# tof.net
KiCad netlist of a schematic drawn in EAGLE
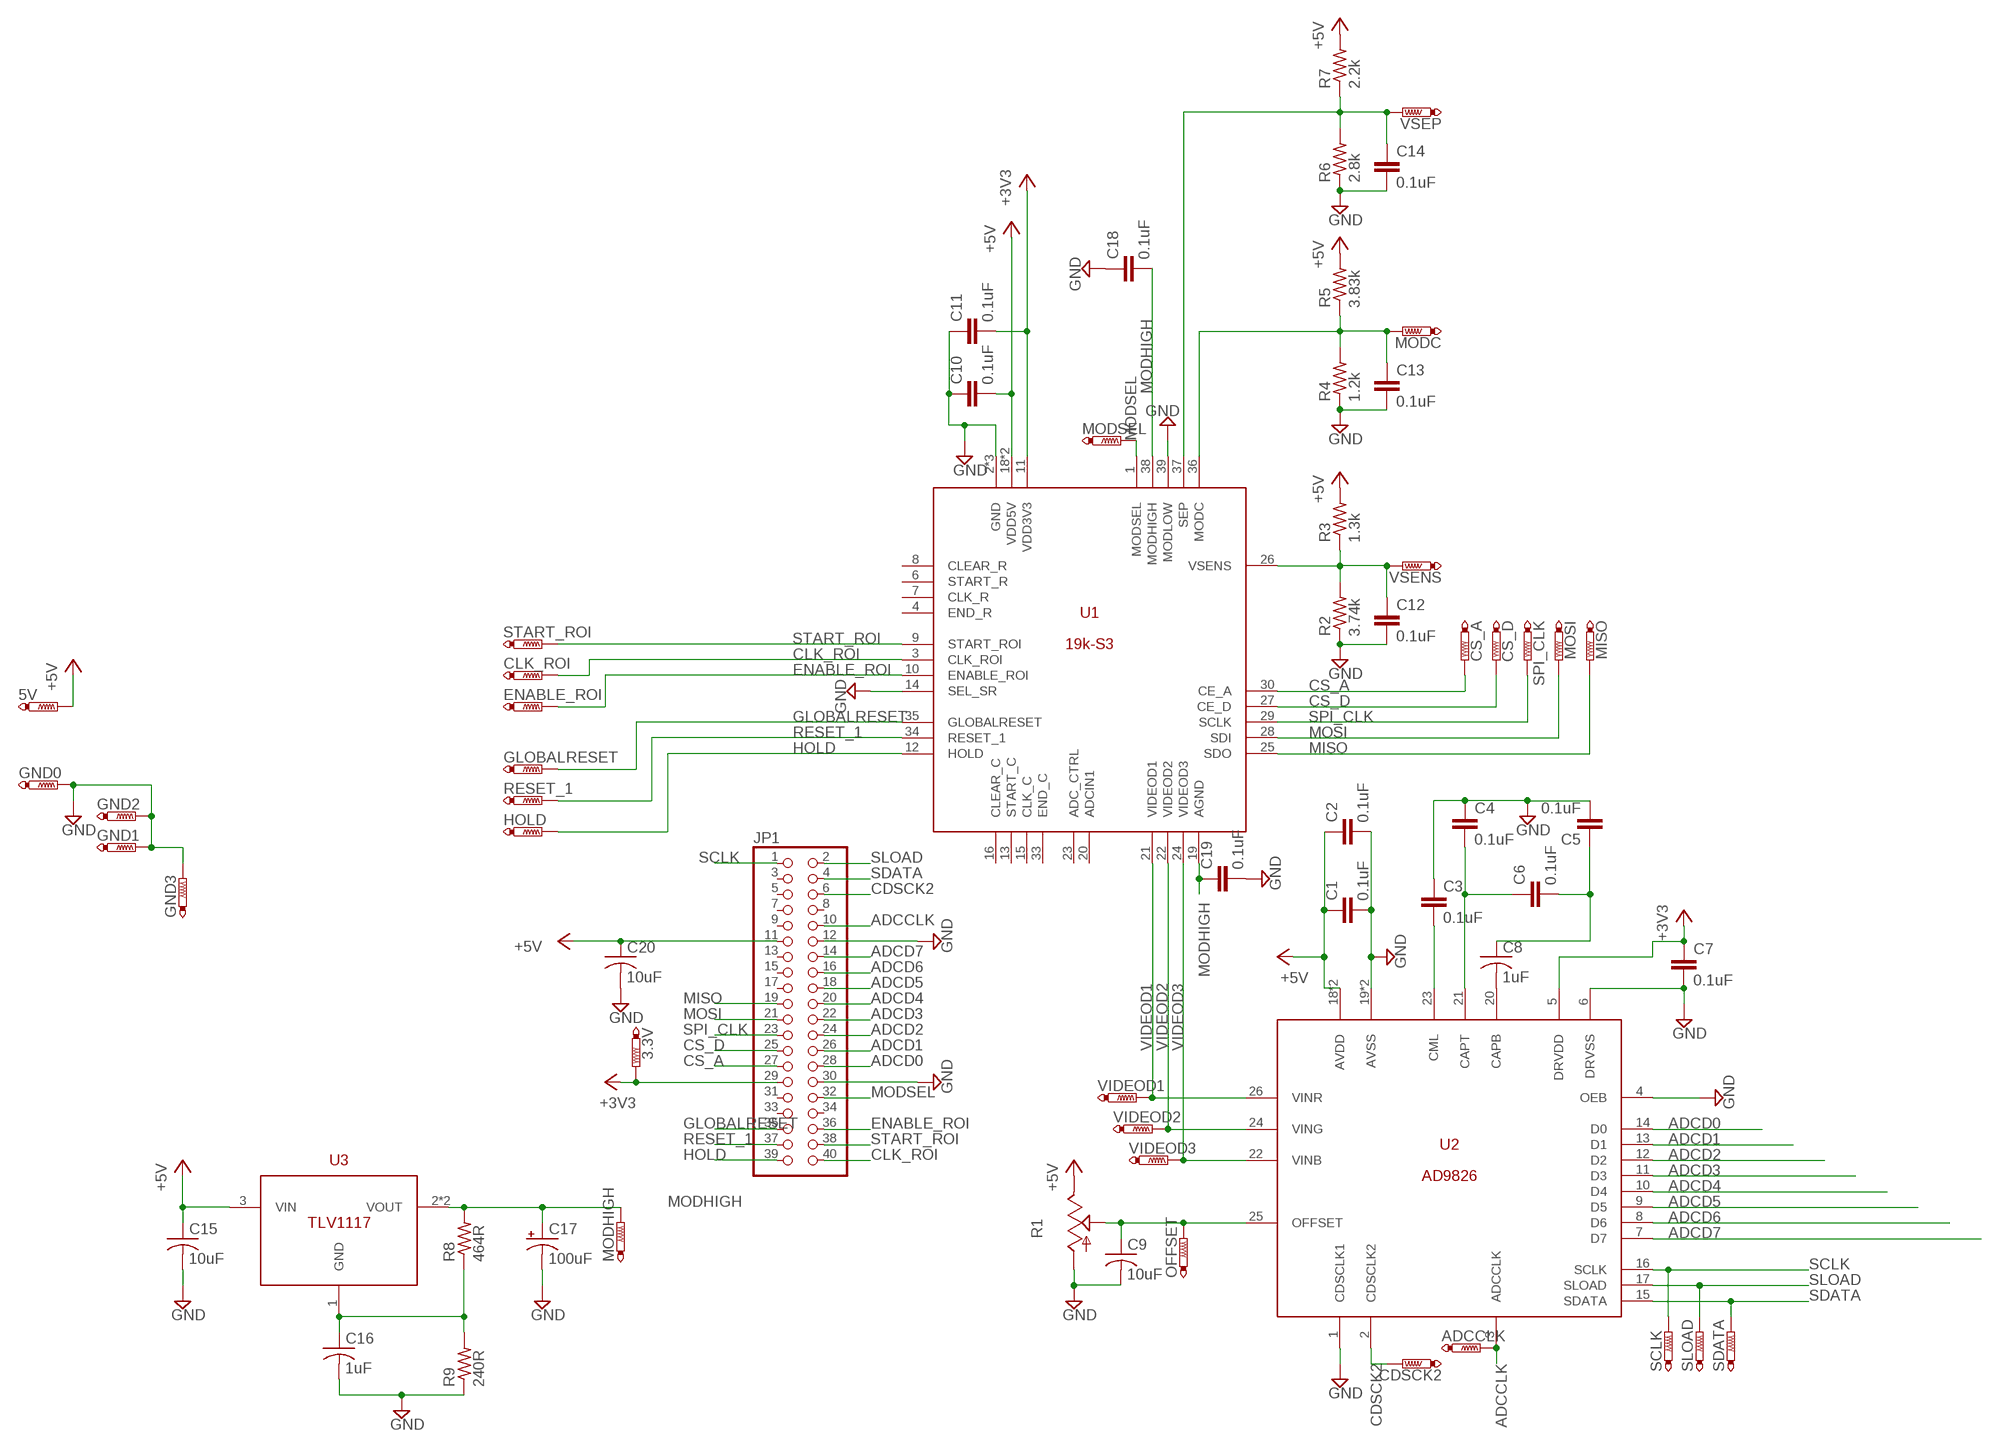
[diagram p0: schematic, sheet 1]

(export (version "E")
  (design (tool "Eeschema 10.0.6"))
  (components
    (comp (ref "3.3V")
      (value "PTR1PAD1-13")
      (footprint "eagle-import:P1-13")
      (libsource (lib "eagle-import") (part "PTR1PAD1-13"))
    )
    (comp (ref "5V")
      (value "PTR1PAD1-13")
      (footprint "eagle-import:P1-13")
      (libsource (lib "eagle-import") (part "PTR1PAD1-13"))
    )
    (comp (ref "ADCCLK")
      (value "PTR1PAD1-13")
      (footprint "eagle-import:P1-13")
      (libsource (lib "eagle-import") (part "PTR1PAD1-13"))
    )
    (comp (ref "C1")
      (value "0.1uF")
      (footprint "eagle-import:C0805")
      (libsource (lib "eagle-import") (part "C-EUC0805"))
    )
    (comp (ref "C2")
      (value "0.1uF")
      (footprint "eagle-import:C0805")
      (libsource (lib "eagle-import") (part "C-EUC0805"))
    )
    (comp (ref "C3")
      (value "0.1uF")
      (footprint "eagle-import:C0805")
      (libsource (lib "eagle-import") (part "C-EUC0805"))
    )
    (comp (ref "C4")
      (value "0.1uF")
      (footprint "eagle-import:C0805")
      (libsource (lib "eagle-import") (part "C-EUC0805"))
    )
    (comp (ref "C5")
      (value "0.1uF")
      (footprint "eagle-import:C0805")
      (libsource (lib "eagle-import") (part "C-EUC0805"))
    )
    (comp (ref "C6")
      (value "0.1uF")
      (footprint "eagle-import:C0805")
      (libsource (lib "eagle-import") (part "C-EUC0805"))
    )
    (comp (ref "C7")
      (value "0.1uF")
      (footprint "eagle-import:C0805")
      (libsource (lib "eagle-import") (part "C-EUC0805"))
    )
    (comp (ref "C8")
      (value "1uF")
      (footprint "eagle-import:C0805")
      (libsource (lib "eagle-import") (part "C-USC0805"))
    )
    (comp (ref "C9")
      (value "10uF")
      (footprint "eagle-import:C0805")
      (libsource (lib "eagle-import") (part "C-USC0805"))
    )
    (comp (ref "C10")
      (value "0.1uF")
      (footprint "eagle-import:C0805")
      (libsource (lib "eagle-import") (part "C-EUC0805"))
    )
    (comp (ref "C11")
      (value "0.1uF")
      (footprint "eagle-import:C0805")
      (libsource (lib "eagle-import") (part "C-EUC0805"))
    )
    (comp (ref "C12")
      (value "0.1uF")
      (footprint "eagle-import:C0805")
      (libsource (lib "eagle-import") (part "C-EUC0805"))
    )
    (comp (ref "C13")
      (value "0.1uF")
      (footprint "eagle-import:C0805")
      (libsource (lib "eagle-import") (part "C-EUC0805"))
    )
    (comp (ref "C14")
      (value "0.1uF")
      (footprint "eagle-import:C0805")
      (libsource (lib "eagle-import") (part "C-EUC0805"))
    )
    (comp (ref "C15")
      (value "10uF")
      (footprint "eagle-import:C0805")
      (libsource (lib "eagle-import") (part "C-USC0805"))
    )
    (comp (ref "C16")
      (value "1uF")
      (footprint "eagle-import:C0805")
      (libsource (lib "eagle-import") (part "C-USC0805"))
    )
    (comp (ref "C17")
      (value "100uF")
      (footprint "eagle-import:PANASONIC_F")
      (libsource (lib "eagle-import") (part "CPOL-USF"))
    )
    (comp (ref "C18")
      (value "0.1uF")
      (footprint "eagle-import:C0805")
      (libsource (lib "eagle-import") (part "C-EUC0805"))
    )
    (comp (ref "C19")
      (value "0.1uF")
      (footprint "eagle-import:C0805")
      (libsource (lib "eagle-import") (part "C-EUC0805"))
    )
    (comp (ref "C20")
      (value "10uF")
      (footprint "eagle-import:C0805")
      (libsource (lib "eagle-import") (part "C-USC0805"))
    )
    (comp (ref "CDSCK2")
      (value "PTR1PAD1-13")
      (footprint "eagle-import:P1-13")
      (libsource (lib "eagle-import") (part "PTR1PAD1-13"))
    )
    (comp (ref "CLK_ROI")
      (value "PTR1PAD1-13")
      (footprint "eagle-import:P1-13")
      (libsource (lib "eagle-import") (part "PTR1PAD1-13"))
    )
    (comp (ref "CS_A")
      (value "PTR1PAD1-13")
      (footprint "eagle-import:P1-13")
      (libsource (lib "eagle-import") (part "PTR1PAD1-13"))
    )
    (comp (ref "CS_D")
      (value "PTR1PAD1-13")
      (footprint "eagle-import:P1-13")
      (libsource (lib "eagle-import") (part "PTR1PAD1-13"))
    )
    (comp (ref "ENABLE_ROI")
      (value "PTR1PAD1-13")
      (footprint "eagle-import:P1-13")
      (libsource (lib "eagle-import") (part "PTR1PAD1-13"))
    )
    (comp (ref "GLOBALRESET")
      (value "PTR1PAD1-13")
      (footprint "eagle-import:P1-13")
      (libsource (lib "eagle-import") (part "PTR1PAD1-13"))
    )
    (comp (ref "GND0")
      (value "PTR1PAD1-13")
      (footprint "eagle-import:P1-13")
      (libsource (lib "eagle-import") (part "PTR1PAD1-13"))
    )
    (comp (ref "GND1")
      (value "PTR1PAD1-13")
      (footprint "eagle-import:P1-13")
      (libsource (lib "eagle-import") (part "PTR1PAD1-13"))
    )
    (comp (ref "GND2")
      (value "PTR1PAD1-13")
      (footprint "eagle-import:P1-13")
      (libsource (lib "eagle-import") (part "PTR1PAD1-13"))
    )
    (comp (ref "GND3")
      (value "PTR1PAD1-13")
      (footprint "eagle-import:P1-13")
      (libsource (lib "eagle-import") (part "PTR1PAD1-13"))
    )
    (comp (ref "HOLD")
      (value "PTR1PAD1-13")
      (footprint "eagle-import:P1-13")
      (libsource (lib "eagle-import") (part "PTR1PAD1-13"))
    )
    (comp (ref "JP1")
      (value "PINHD-2X20")
      (footprint "eagle-import:SMD-40")
      (libsource (lib "eagle-import") (part "PINHD-2X20"))
    )
    (comp (ref "MISO")
      (value "PTR1PAD1-13")
      (footprint "eagle-import:P1-13")
      (libsource (lib "eagle-import") (part "PTR1PAD1-13"))
    )
    (comp (ref "MODC")
      (value "PTR1PAD1-13")
      (footprint "eagle-import:P1-13")
      (libsource (lib "eagle-import") (part "PTR1PAD1-13"))
    )
    (comp (ref "MODHIGH")
      (value "PTR1PAD1-13")
      (footprint "eagle-import:P1-13")
      (libsource (lib "eagle-import") (part "PTR1PAD1-13"))
    )
    (comp (ref "MODSEL")
      (value "PTR1PAD1-13")
      (footprint "eagle-import:P1-13")
      (libsource (lib "eagle-import") (part "PTR1PAD1-13"))
    )
    (comp (ref "MOSI")
      (value "PTR1PAD1-13")
      (footprint "eagle-import:P1-13")
      (libsource (lib "eagle-import") (part "PTR1PAD1-13"))
    )
    (comp (ref "OFFSET")
      (value "PTR1PAD1-13")
      (footprint "eagle-import:P1-13")
      (libsource (lib "eagle-import") (part "PTR1PAD1-13"))
    )
    (comp (ref "R1")
      (value "TRIM_US-S63P")
      (footprint "eagle-import:S63P")
      (libsource (lib "eagle-import") (part "TRIM_US-S63P"))
    )
    (comp (ref "R2")
      (value "3.74k")
      (footprint "eagle-import:R0805")
      (libsource (lib "eagle-import") (part "R-US_R0805"))
    )
    (comp (ref "R3")
      (value "1.3k")
      (footprint "eagle-import:R0805")
      (libsource (lib "eagle-import") (part "R-US_R0805"))
    )
    (comp (ref "R4")
      (value "1.2k")
      (footprint "eagle-import:R0805")
      (libsource (lib "eagle-import") (part "R-US_R0805"))
    )
    (comp (ref "R5")
      (value "3.83k")
      (footprint "eagle-import:R0805")
      (libsource (lib "eagle-import") (part "R-US_R0805"))
    )
    (comp (ref "R6")
      (value "2.8k")
      (footprint "eagle-import:R0805")
      (libsource (lib "eagle-import") (part "R-US_R0805"))
    )
    (comp (ref "R7")
      (value "2.2k")
      (footprint "eagle-import:R0805")
      (libsource (lib "eagle-import") (part "R-US_R0805"))
    )
    (comp (ref "R8")
      (value "464R")
      (footprint "eagle-import:R0805")
      (libsource (lib "eagle-import") (part "R-US_R0805"))
    )
    (comp (ref "R9")
      (value "240R")
      (footprint "eagle-import:R0805")
      (libsource (lib "eagle-import") (part "R-US_R0805"))
    )
    (comp (ref "RESET_1")
      (value "PTR1PAD1-13")
      (footprint "eagle-import:P1-13")
      (libsource (lib "eagle-import") (part "PTR1PAD1-13"))
    )
    (comp (ref "SCLK")
      (value "PTR1PAD1-13")
      (footprint "eagle-import:P1-13")
      (libsource (lib "eagle-import") (part "PTR1PAD1-13"))
    )
    (comp (ref "SDATA")
      (value "PTR1PAD1-13")
      (footprint "eagle-import:P1-13")
      (libsource (lib "eagle-import") (part "PTR1PAD1-13"))
    )
    (comp (ref "SLOAD")
      (value "PTR1PAD1-13")
      (footprint "eagle-import:P1-13")
      (libsource (lib "eagle-import") (part "PTR1PAD1-13"))
    )
    (comp (ref "SPI_CLK")
      (value "PTR1PAD1-13")
      (footprint "eagle-import:P1-13")
      (libsource (lib "eagle-import") (part "PTR1PAD1-13"))
    )
    (comp (ref "START_ROI")
      (value "PTR1PAD1-13")
      (footprint "eagle-import:P1-13")
      (libsource (lib "eagle-import") (part "PTR1PAD1-13"))
    )
    (comp (ref "U1")
      (value "19K-S3")
      (footprint "eagle-import:TLCC40")
      (libsource (lib "eagle-import") (part "19K-S3"))
    )
    (comp (ref "U2")
      (value "AD9826")
      (footprint "eagle-import:SSOP28")
      (libsource (lib "eagle-import") (part "AD9826"))
    )
    (comp (ref "U3")
      (value "TLV1117")
      (footprint "eagle-import:SOT223")
      (libsource (lib "eagle-import") (part "TLV1117"))
    )
    (comp (ref "VIDEOD1")
      (value "PTR1PAD1-13")
      (footprint "eagle-import:P1-13")
      (libsource (lib "eagle-import") (part "PTR1PAD1-13"))
    )
    (comp (ref "VIDEOD2")
      (value "PTR1PAD1-13")
      (footprint "eagle-import:P1-13")
      (libsource (lib "eagle-import") (part "PTR1PAD1-13"))
    )
    (comp (ref "VIDEOD3")
      (value "PTR1PAD1-13")
      (footprint "eagle-import:P1-13")
      (libsource (lib "eagle-import") (part "PTR1PAD1-13"))
    )
    (comp (ref "VSENS")
      (value "PTR1PAD1-13")
      (footprint "eagle-import:P1-13")
      (libsource (lib "eagle-import") (part "PTR1PAD1-13"))
    )
    (comp (ref "VSEP")
      (value "PTR1PAD1-13")
      (footprint "eagle-import:P1-13")
      (libsource (lib "eagle-import") (part "PTR1PAD1-13"))
    )
  )
  (nets
    (net (code "1") (name "+3V3") (class "Default")
      (node (ref "3.3V") (pin "TP") (pinfunction "TP_TP") (pintype "input"))
      (node (ref "C11") (pin "2") (pinfunction "2_2") (pintype "passive"))
      (node (ref "C7") (pin "1") (pinfunction "1_1") (pintype "passive"))
      (node (ref "JP1") (pin "29") (pinfunction "29_29") (pintype "passive"))
      (node (ref "U1") (pin "11") (pinfunction "VDD3V3_11") (pintype "power_in"))
      (node (ref "U2") (pin "5") (pinfunction "DRVDD_5") (pintype "power_in"))
    )
    (net (code "2") (name "+5V") (class "Default")
      (node (ref "5V") (pin "TP") (pinfunction "TP_TP") (pintype "input"))
      (node (ref "C1") (pin "1") (pinfunction "1_1") (pintype "passive"))
      (node (ref "C10") (pin "2") (pinfunction "2_2") (pintype "passive"))
      (node (ref "C15") (pin "1") (pinfunction "1_1") (pintype "passive"))
      (node (ref "C2") (pin "1") (pinfunction "1_1") (pintype "passive"))
      (node (ref "C20") (pin "1") (pinfunction "1_1") (pintype "passive"))
      (node (ref "JP1") (pin "11") (pinfunction "11_11") (pintype "passive"))
      (node (ref "R1") (pin "E") (pinfunction "E_E") (pintype "passive"))
      (node (ref "R3") (pin "2") (pinfunction "2_2") (pintype "passive"))
      (node (ref "R5") (pin "2") (pinfunction "2_2") (pintype "passive"))
      (node (ref "R7") (pin "2") (pinfunction "2_2") (pintype "passive"))
      (node (ref "U1") (pin "18") (pinfunction "VDD5V_18") (pintype "power_in"))
      (node (ref "U1") (pin "40") (pinfunction "VDD5V_40") (pintype "power_in"))
      (node (ref "U2") (pin "18") (pinfunction "AVDD_18") (pintype "power_in"))
      (node (ref "U2") (pin "28") (pinfunction "AVDD_28") (pintype "power_in"))
      (node (ref "U3") (pin "3") (pinfunction "VIN_3") (pintype "power_in"))
    )
    (net (code "3") (name "/ADCCLK") (class "Default")
      (node (ref "ADCCLK") (pin "TP") (pinfunction "TP_TP") (pintype "input"))
      (node (ref "JP1") (pin "10") (pinfunction "10_10") (pintype "passive"))
      (node (ref "U2") (pin "3") (pinfunction "ADCCLK_3") (pintype "input"))
    )
    (net (code "4") (name "/ADCD0") (class "Default")
      (node (ref "JP1") (pin "28") (pinfunction "28_28") (pintype "passive"))
      (node (ref "U2") (pin "14") (pinfunction "D0_14") (pintype "bidirectional"))
    )
    (net (code "5") (name "/ADCD1") (class "Default")
      (node (ref "JP1") (pin "26") (pinfunction "26_26") (pintype "passive"))
      (node (ref "U2") (pin "13") (pinfunction "D1_13") (pintype "bidirectional"))
    )
    (net (code "6") (name "/ADCD2") (class "Default")
      (node (ref "JP1") (pin "24") (pinfunction "24_24") (pintype "passive"))
      (node (ref "U2") (pin "12") (pinfunction "D2_12") (pintype "bidirectional"))
    )
    (net (code "7") (name "/ADCD3") (class "Default")
      (node (ref "JP1") (pin "22") (pinfunction "22_22") (pintype "passive"))
      (node (ref "U2") (pin "11") (pinfunction "D3_11") (pintype "bidirectional"))
    )
    (net (code "8") (name "/ADCD4") (class "Default")
      (node (ref "JP1") (pin "20") (pinfunction "20_20") (pintype "passive"))
      (node (ref "U2") (pin "10") (pinfunction "D4_10") (pintype "bidirectional"))
    )
    (net (code "9") (name "/ADCD5") (class "Default")
      (node (ref "JP1") (pin "18") (pinfunction "18_18") (pintype "passive"))
      (node (ref "U2") (pin "9") (pinfunction "D5_9") (pintype "bidirectional"))
    )
    (net (code "10") (name "/ADCD6") (class "Default")
      (node (ref "JP1") (pin "16") (pinfunction "16_16") (pintype "passive"))
      (node (ref "U2") (pin "8") (pinfunction "D6_8") (pintype "bidirectional"))
    )
    (net (code "11") (name "/ADCD7") (class "Default")
      (node (ref "JP1") (pin "14") (pinfunction "14_14") (pintype "passive"))
      (node (ref "U2") (pin "7") (pinfunction "D7_7") (pintype "bidirectional"))
    )
    (net (code "12") (name "/CDSCK2") (class "Default")
      (node (ref "CDSCK2") (pin "TP") (pinfunction "TP_TP") (pintype "input"))
      (node (ref "JP1") (pin "6") (pinfunction "6_6") (pintype "passive"))
      (node (ref "U2") (pin "2") (pinfunction "CDSCLK2_2") (pintype "input"))
    )
    (net (code "13") (name "/CLK_ROI") (class "Default")
      (node (ref "CLK_ROI") (pin "TP") (pinfunction "TP_TP") (pintype "input"))
      (node (ref "JP1") (pin "40") (pinfunction "40_40") (pintype "passive"))
      (node (ref "U1") (pin "3") (pinfunction "CLK_ROI_3") (pintype "input"))
    )
    (net (code "14") (name "/CS_A") (class "Default")
      (node (ref "CS_A") (pin "TP") (pinfunction "TP_TP") (pintype "input"))
      (node (ref "JP1") (pin "27") (pinfunction "27_27") (pintype "passive"))
      (node (ref "U1") (pin "30") (pinfunction "CE_A_30") (pintype "input"))
    )
    (net (code "15") (name "/CS_D") (class "Default")
      (node (ref "CS_D") (pin "TP") (pinfunction "TP_TP") (pintype "input"))
      (node (ref "JP1") (pin "25") (pinfunction "25_25") (pintype "passive"))
      (node (ref "U1") (pin "27") (pinfunction "CE_D_27") (pintype "input"))
    )
    (net (code "16") (name "/ENABLE_ROI") (class "Default")
      (node (ref "ENABLE_ROI") (pin "TP") (pinfunction "TP_TP") (pintype "input"))
      (node (ref "JP1") (pin "36") (pinfunction "36_36") (pintype "passive"))
      (node (ref "U1") (pin "10") (pinfunction "ENABLE_ROI_10") (pintype "output"))
    )
    (net (code "17") (name "/GLOBALRESET") (class "Default")
      (node (ref "GLOBALRESET") (pin "TP") (pinfunction "TP_TP") (pintype "input"))
      (node (ref "JP1") (pin "35") (pinfunction "35_35") (pintype "passive"))
      (node (ref "U1") (pin "35") (pinfunction "GLOBALRESET_35") (pintype "input"))
    )
    (net (code "18") (name "/HOLD") (class "Default")
      (node (ref "HOLD") (pin "TP") (pinfunction "TP_TP") (pintype "input"))
      (node (ref "JP1") (pin "39") (pinfunction "39_39") (pintype "passive"))
      (node (ref "U1") (pin "12") (pinfunction "HOLD_12") (pintype "input"))
    )
    (net (code "19") (name "/MISO") (class "Default")
      (node (ref "JP1") (pin "19") (pinfunction "19_19") (pintype "passive"))
      (node (ref "MISO") (pin "TP") (pinfunction "TP_TP") (pintype "input"))
      (node (ref "U1") (pin "25") (pinfunction "SDO_25") (pintype "output"))
    )
    (net (code "20") (name "/MODHIGH") (class "Default")
      (node (ref "C17") (pin "+") (pinfunction "+_+") (pintype "passive"))
      (node (ref "C18") (pin "2") (pinfunction "2_2") (pintype "passive"))
      (node (ref "C19") (pin "1") (pinfunction "1_1") (pintype "passive"))
      (node (ref "MODHIGH") (pin "TP") (pinfunction "TP_TP") (pintype "input"))
      (node (ref "R8") (pin "2") (pinfunction "2_2") (pintype "passive"))
      (node (ref "U1") (pin "19") (pinfunction "AGND_19") (pintype "power_in"))
      (node (ref "U1") (pin "38") (pinfunction "MODHIGH_38") (pintype "power_in"))
      (node (ref "U3") (pin "2") (pinfunction "VOUT_2") (pintype "output"))
      (node (ref "U3") (pin "4") (pinfunction "VOUT_4") (pintype "output"))
    )
    (net (code "21") (name "/MODSEL") (class "Default")
      (node (ref "JP1") (pin "32") (pinfunction "32_32") (pintype "passive"))
      (node (ref "MODSEL") (pin "TP") (pinfunction "TP_TP") (pintype "input"))
      (node (ref "U1") (pin "1") (pinfunction "MODSEL_1") (pintype "input"))
    )
    (net (code "22") (name "/MOSI") (class "Default")
      (node (ref "JP1") (pin "21") (pinfunction "21_21") (pintype "passive"))
      (node (ref "MOSI") (pin "TP") (pinfunction "TP_TP") (pintype "input"))
      (node (ref "U1") (pin "28") (pinfunction "SDI_28") (pintype "input"))
    )
    (net (code "23") (name "/RESET_1") (class "Default")
      (node (ref "JP1") (pin "37") (pinfunction "37_37") (pintype "passive"))
      (node (ref "RESET_1") (pin "TP") (pinfunction "TP_TP") (pintype "input"))
      (node (ref "U1") (pin "34") (pinfunction "RESET_1_34") (pintype "input"))
    )
    (net (code "24") (name "/SCLK") (class "Default")
      (node (ref "JP1") (pin "1") (pinfunction "1_1") (pintype "passive"))
      (node (ref "SCLK") (pin "TP") (pinfunction "TP_TP") (pintype "input"))
      (node (ref "U2") (pin "16") (pinfunction "SCLK_16") (pintype "input"))
    )
    (net (code "25") (name "/SDATA") (class "Default")
      (node (ref "JP1") (pin "4") (pinfunction "4_4") (pintype "passive"))
      (node (ref "SDATA") (pin "TP") (pinfunction "TP_TP") (pintype "input"))
      (node (ref "U2") (pin "15") (pinfunction "SDATA_15") (pintype "bidirectional"))
    )
    (net (code "26") (name "/SLOAD") (class "Default")
      (node (ref "JP1") (pin "2") (pinfunction "2_2") (pintype "passive"))
      (node (ref "SLOAD") (pin "TP") (pinfunction "TP_TP") (pintype "input"))
      (node (ref "U2") (pin "17") (pinfunction "SLOAD_17") (pintype "input"))
    )
    (net (code "27") (name "/SPI_CLK") (class "Default")
      (node (ref "JP1") (pin "23") (pinfunction "23_23") (pintype "passive"))
      (node (ref "SPI_CLK") (pin "TP") (pinfunction "TP_TP") (pintype "input"))
      (node (ref "U1") (pin "29") (pinfunction "SCLK_29") (pintype "input"))
    )
    (net (code "28") (name "/START_ROI") (class "Default")
      (node (ref "JP1") (pin "38") (pinfunction "38_38") (pintype "passive"))
      (node (ref "START_ROI") (pin "TP") (pinfunction "TP_TP") (pintype "input"))
      (node (ref "U1") (pin "9") (pinfunction "START_ROI_9") (pintype "input"))
    )
    (net (code "29") (name "/VIDEOD1") (class "Default")
      (node (ref "U1") (pin "21") (pinfunction "VIDEOD1_21") (pintype "output"))
      (node (ref "U2") (pin "26") (pinfunction "VINR_26") (pintype "input"))
      (node (ref "VIDEOD1") (pin "TP") (pinfunction "TP_TP") (pintype "input"))
    )
    (net (code "30") (name "/VIDEOD2") (class "Default")
      (node (ref "U1") (pin "22") (pinfunction "VIDEOD2_22") (pintype "output"))
      (node (ref "U2") (pin "24") (pinfunction "VING_24") (pintype "input"))
      (node (ref "VIDEOD2") (pin "TP") (pinfunction "TP_TP") (pintype "input"))
    )
    (net (code "31") (name "/VIDEOD3") (class "Default")
      (node (ref "U1") (pin "24") (pinfunction "VIDEOD3_24") (pintype "output"))
      (node (ref "U2") (pin "22") (pinfunction "VINB_22") (pintype "input"))
      (node (ref "VIDEOD3") (pin "TP") (pinfunction "TP_TP") (pintype "input"))
    )
    (net (code "32") (name "GND") (class "Default")
      (node (ref "C1") (pin "2") (pinfunction "2_2") (pintype "passive"))
      (node (ref "C10") (pin "1") (pinfunction "1_1") (pintype "passive"))
      (node (ref "C11") (pin "1") (pinfunction "1_1") (pintype "passive"))
      (node (ref "C12") (pin "2") (pinfunction "2_2") (pintype "passive"))
      (node (ref "C13") (pin "2") (pinfunction "2_2") (pintype "passive"))
      (node (ref "C14") (pin "2") (pinfunction "2_2") (pintype "passive"))
      (node (ref "C15") (pin "2") (pinfunction "2_2") (pintype "passive"))
      (node (ref "C16") (pin "2") (pinfunction "2_2") (pintype "passive"))
      (node (ref "C17") (pin "-") (pinfunction "-_-") (pintype "passive"))
      (node (ref "C18") (pin "1") (pinfunction "1_1") (pintype "passive"))
      (node (ref "C19") (pin "2") (pinfunction "2_2") (pintype "passive"))
      (node (ref "C2") (pin "2") (pinfunction "2_2") (pintype "passive"))
      (node (ref "C20") (pin "2") (pinfunction "2_2") (pintype "passive"))
      (node (ref "C3") (pin "1") (pinfunction "1_1") (pintype "passive"))
      (node (ref "C4") (pin "1") (pinfunction "1_1") (pintype "passive"))
      (node (ref "C5") (pin "2") (pinfunction "2_2") (pintype "passive"))
      (node (ref "C7") (pin "2") (pinfunction "2_2") (pintype "passive"))
      (node (ref "C9") (pin "2") (pinfunction "2_2") (pintype "passive"))
      (node (ref "GND0") (pin "TP") (pinfunction "TP_TP") (pintype "input"))
      (node (ref "GND1") (pin "TP") (pinfunction "TP_TP") (pintype "input"))
      (node (ref "GND2") (pin "TP") (pinfunction "TP_TP") (pintype "input"))
      (node (ref "GND3") (pin "TP") (pinfunction "TP_TP") (pintype "input"))
      (node (ref "JP1") (pin "12") (pinfunction "12_12") (pintype "passive"))
      (node (ref "JP1") (pin "30") (pinfunction "30_30") (pintype "passive"))
      (node (ref "R1") (pin "A") (pinfunction "A_A") (pintype "passive"))
      (node (ref "R2") (pin "1") (pinfunction "1_1") (pintype "passive"))
      (node (ref "R4") (pin "1") (pinfunction "1_1") (pintype "passive"))
      (node (ref "R6") (pin "1") (pinfunction "1_1") (pintype "passive"))
      (node (ref "R9") (pin "1") (pinfunction "1_1") (pintype "passive"))
      (node (ref "U1") (pin "14") (pinfunction "SEL_SR_14") (pintype "input"))
      (node (ref "U1") (pin "2") (pinfunction "GND_2") (pintype "power_in"))
      (node (ref "U1") (pin "39") (pinfunction "MODLOW_39") (pintype "power_in"))
      (node (ref "U1") (pin "5") (pinfunction "GND_5") (pintype "power_in"))
      (node (ref "U1") (pin "PAD") (pinfunction "GND_PAD") (pintype "power_in"))
      (node (ref "U2") (pin "1") (pinfunction "CDSCLK1_1") (pintype "input"))
      (node (ref "U2") (pin "19") (pinfunction "AVSS_19") (pintype "power_in"))
      (node (ref "U2") (pin "27") (pinfunction "AVSS_27") (pintype "power_in"))
      (node (ref "U2") (pin "4") (pinfunction "OEB_4") (pintype "input"))
      (node (ref "U2") (pin "6") (pinfunction "DRVSS_6") (pintype "power_in"))
    )
    (net (code "33") (name "Net-(C5-Pad1)") (class "Default")
      (node (ref "C5") (pin "1") (pinfunction "1_1") (pintype "passive"))
      (node (ref "C6") (pin "2") (pinfunction "2_2") (pintype "passive"))
      (node (ref "C8") (pin "1") (pinfunction "1_1") (pintype "passive"))
    )
    (net (code "34") (name "Net-(U1-MODC)") (class "Default")
      (node (ref "C13") (pin "1") (pinfunction "1_1") (pintype "passive"))
      (node (ref "MODC") (pin "TP") (pinfunction "TP_TP") (pintype "input"))
      (node (ref "R4") (pin "2") (pinfunction "2_2") (pintype "passive"))
      (node (ref "R5") (pin "1") (pinfunction "1_1") (pintype "passive"))
      (node (ref "U1") (pin "36") (pinfunction "MODC_36") (pintype "input"))
    )
    (net (code "35") (name "Net-(U1-SEP)") (class "Default")
      (node (ref "C14") (pin "1") (pinfunction "1_1") (pintype "passive"))
      (node (ref "R6") (pin "2") (pinfunction "2_2") (pintype "passive"))
      (node (ref "R7") (pin "1") (pinfunction "1_1") (pintype "passive"))
      (node (ref "U1") (pin "37") (pinfunction "SEP_37") (pintype "input"))
      (node (ref "VSEP") (pin "TP") (pinfunction "TP_TP") (pintype "input"))
    )
    (net (code "36") (name "Net-(U1-VSENS)") (class "Default")
      (node (ref "C12") (pin "1") (pinfunction "1_1") (pintype "passive"))
      (node (ref "R2") (pin "2") (pinfunction "2_2") (pintype "passive"))
      (node (ref "R3") (pin "1") (pinfunction "1_1") (pintype "passive"))
      (node (ref "U1") (pin "26") (pinfunction "VSENS_26") (pintype "input"))
      (node (ref "VSENS") (pin "TP") (pinfunction "TP_TP") (pintype "input"))
    )
    (net (code "37") (name "Net-(U2-CAPB)") (class "Default")
      (node (ref "C8") (pin "2") (pinfunction "2_2") (pintype "passive"))
      (node (ref "U2") (pin "20") (pinfunction "CAPB_20") (pintype "input"))
    )
    (net (code "38") (name "Net-(U2-CAPT)") (class "Default")
      (node (ref "C4") (pin "2") (pinfunction "2_2") (pintype "passive"))
      (node (ref "C6") (pin "1") (pinfunction "1_1") (pintype "passive"))
      (node (ref "U2") (pin "21") (pinfunction "CAPT_21") (pintype "input"))
    )
    (net (code "39") (name "Net-(U2-CML)") (class "Default")
      (node (ref "C3") (pin "2") (pinfunction "2_2") (pintype "passive"))
      (node (ref "U2") (pin "23") (pinfunction "CML_23") (pintype "input"))
    )
    (net (code "40") (name "Net-(U2-OFFSET)") (class "Default")
      (node (ref "C9") (pin "1") (pinfunction "1_1") (pintype "passive"))
      (node (ref "OFFSET") (pin "TP") (pinfunction "TP_TP") (pintype "input"))
      (node (ref "R1") (pin "S") (pinfunction "S_S") (pintype "passive"))
      (node (ref "U2") (pin "25") (pinfunction "OFFSET_25") (pintype "input"))
    )
    (net (code "41") (name "Net-(U3-GND)") (class "Default")
      (node (ref "C16") (pin "1") (pinfunction "1_1") (pintype "passive"))
      (node (ref "R8") (pin "1") (pinfunction "1_1") (pintype "passive"))
      (node (ref "R9") (pin "2") (pinfunction "2_2") (pintype "passive"))
      (node (ref "U3") (pin "1") (pinfunction "GND_1") (pintype "power_in"))
    )
    (net (code "42") (name "unconnected-(JP1-Pad3)") (class "Default")
      (node (ref "JP1") (pin "3") (pinfunction "3_3") (pintype "passive"))
    )
    (net (code "43") (name "unconnected-(JP1-Pad5)") (class "Default")
      (node (ref "JP1") (pin "5") (pinfunction "5_5") (pintype "passive"))
    )
    (net (code "44") (name "unconnected-(JP1-Pad7)") (class "Default")
      (node (ref "JP1") (pin "7") (pinfunction "7_7") (pintype "passive"))
    )
    (net (code "45") (name "unconnected-(JP1-Pad8)") (class "Default")
      (node (ref "JP1") (pin "8") (pinfunction "8_8") (pintype "passive"))
    )
    (net (code "46") (name "unconnected-(JP1-Pad9)") (class "Default")
      (node (ref "JP1") (pin "9") (pinfunction "9_9") (pintype "passive"))
    )
    (net (code "47") (name "unconnected-(JP1-Pad13)") (class "Default")
      (node (ref "JP1") (pin "13") (pinfunction "13_13") (pintype "passive"))
    )
    (net (code "48") (name "unconnected-(JP1-Pad15)") (class "Default")
      (node (ref "JP1") (pin "15") (pinfunction "15_15") (pintype "passive"))
    )
    (net (code "49") (name "unconnected-(JP1-Pad17)") (class "Default")
      (node (ref "JP1") (pin "17") (pinfunction "17_17") (pintype "passive"))
    )
    (net (code "50") (name "unconnected-(JP1-Pad31)") (class "Default")
      (node (ref "JP1") (pin "31") (pinfunction "31_31") (pintype "passive"))
    )
    (net (code "51") (name "unconnected-(JP1-Pad33)") (class "Default")
      (node (ref "JP1") (pin "33") (pinfunction "33_33") (pintype "passive"))
    )
    (net (code "52") (name "unconnected-(JP1-Pad34)") (class "Default")
      (node (ref "JP1") (pin "34") (pinfunction "34_34") (pintype "passive"))
    )
    (net (code "53") (name "unconnected-(U1-ADCIN1-Pad20)") (class "Default")
      (node (ref "U1") (pin "20") (pinfunction "ADCIN1_20") (pintype "input"))
    )
    (net (code "54") (name "unconnected-(U1-ADC_CTRL-Pad23)") (class "Default")
      (node (ref "U1") (pin "23") (pinfunction "ADC_CTRL_23") (pintype "input"))
    )
    (net (code "55") (name "unconnected-(U1-CLEAR_C-Pad16)") (class "Default")
      (node (ref "U1") (pin "16") (pinfunction "CLEAR_C_16") (pintype "input"))
    )
    (net (code "56") (name "unconnected-(U1-CLEAR_R-Pad8)") (class "Default")
      (node (ref "U1") (pin "8") (pinfunction "CLEAR_R_8") (pintype "input"))
    )
    (net (code "57") (name "unconnected-(U1-CLK_C-Pad15)") (class "Default")
      (node (ref "U1") (pin "15") (pinfunction "CLK_C_15") (pintype "input"))
    )
    (net (code "58") (name "unconnected-(U1-CLK_R-Pad7)") (class "Default")
      (node (ref "U1") (pin "7") (pinfunction "CLK_R_7") (pintype "input"))
    )
    (net (code "59") (name "unconnected-(U1-END_C-Pad33)") (class "Default")
      (node (ref "U1") (pin "33") (pinfunction "END_C_33") (pintype "output"))
    )
    (net (code "60") (name "unconnected-(U1-END_R-Pad4)") (class "Default")
      (node (ref "U1") (pin "4") (pinfunction "END_R_4") (pintype "output"))
    )
    (net (code "61") (name "unconnected-(U1-START_C-Pad13)") (class "Default")
      (node (ref "U1") (pin "13") (pinfunction "START_C_13") (pintype "input"))
    )
    (net (code "62") (name "unconnected-(U1-START_R-Pad6)") (class "Default")
      (node (ref "U1") (pin "6") (pinfunction "START_R_6") (pintype "input"))
    )
  )
)
